# BATT_CONNECTOR.net
KiCad netlist of a schematic drawn in EAGLE
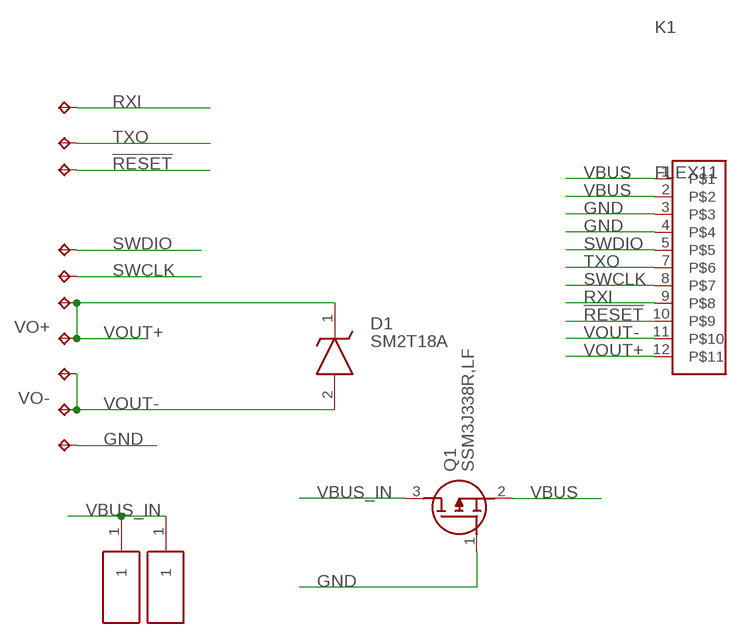
[diagram p0: schematic, sheet 1]

(export (version "E")
  (design (tool "Eeschema 10.0.6"))
  (components
    (comp (ref "!RESET")
      (value "TPB2,54")
      (footprint "eagle-import:B2,54")
      (libsource (lib "eagle-import") (part "TPB2,54"))
    )
    (comp (ref "D1")
      (value "SM2T18A")
      (footprint "eagle-import:SM2T18A")
      (fields (field (name "MOUSER_PART_NUMBER") "511-SM2T18A"))
      (libsource (lib "eagle-import") (part "SM2T18A"))
    )
    (comp (ref "GND")
      (value "TPB2,54")
      (footprint "eagle-import:B2,54")
      (libsource (lib "eagle-import") (part "TPB2,54"))
    )
    (comp (ref "H1")
      (value "S1761-42R")
      (footprint "eagle-import:S176142R")
      (fields (field (name "MOUSER_PART_NUMBER") "855-S1761-42R"))
      (libsource (lib "eagle-import") (part "S1761-42R"))
    )
    (comp (ref "H2")
      (value "S1761-42R")
      (footprint "eagle-import:S176142R")
      (fields (field (name "MOUSER_PART_NUMBER") "855-S1761-42R"))
      (libsource (lib "eagle-import") (part "S1761-42R"))
    )
    (comp (ref "K1")
      (value "FLEX11")
      (footprint "eagle-import:FLEX11")
      (libsource (lib "eagle-import") (part "FLEX11"))
    )
    (comp (ref "Q1")
      (value "SSM3J338R,LF")
      (footprint "eagle-import:SSM3J332RLFT")
      (fields (field (name "MOUSER_PART_NUMBER") "757-SSM3J338RLF"))
      (libsource (lib "eagle-import") (part "SSM3J338R,LF"))
    )
    (comp (ref "RXI")
      (value "TPB2,54")
      (footprint "eagle-import:B2,54")
      (libsource (lib "eagle-import") (part "TPB2,54"))
    )
    (comp (ref "SWCLK")
      (value "TPB2,54")
      (footprint "eagle-import:B2,54")
      (libsource (lib "eagle-import") (part "TPB2,54"))
    )
    (comp (ref "SWDIO")
      (value "TPB2,54")
      (footprint "eagle-import:B2,54")
      (libsource (lib "eagle-import") (part "TPB2,54"))
    )
    (comp (ref "TXO")
      (value "TPB2,54")
      (footprint "eagle-import:B2,54")
      (libsource (lib "eagle-import") (part "TPB2,54"))
    )
    (comp (ref "VO+")
      (value "TPB2,54")
      (footprint "eagle-import:B2,54")
      (libsource (lib "eagle-import") (part "TPB2,54"))
    )
    (comp (ref "VO-")
      (value "TPB2,54")
      (footprint "eagle-import:B2,54")
      (libsource (lib "eagle-import") (part "TPB2,54"))
    )
    (comp (ref "VOUT+1")
      (value "TPB2,54")
      (footprint "eagle-import:B2,54")
      (libsource (lib "eagle-import") (part "TPB2,54"))
    )
    (comp (ref "VOUT-1")
      (value "TPB2,54")
      (footprint "eagle-import:B2,54")
      (libsource (lib "eagle-import") (part "TPB2,54"))
    )
  )
  (nets
    (net (code "1") (name "/GND") (class "Default")
      (node (ref "GND") (pin "TP") (pinfunction "TP_TP") (pintype "input"))
      (node (ref "K1") (pin "3") (pinfunction "P$3_3") (pintype "bidirectional"))
      (node (ref "K1") (pin "4") (pinfunction "P$4_4") (pintype "bidirectional"))
      (node (ref "Q1") (pin "1") (pinfunction "G_1") (pintype "bidirectional"))
    )
    (net (code "2") (name "/RXI") (class "Default")
      (node (ref "K1") (pin "9") (pinfunction "P$8_9") (pintype "bidirectional"))
      (node (ref "RXI") (pin "TP") (pinfunction "TP_TP") (pintype "input"))
    )
    (net (code "3") (name "/SWCLK") (class "Default")
      (node (ref "K1") (pin "8") (pinfunction "P$7_8") (pintype "bidirectional"))
      (node (ref "SWCLK") (pin "TP") (pinfunction "TP_TP") (pintype "input"))
    )
    (net (code "4") (name "/SWDIO") (class "Default")
      (node (ref "K1") (pin "5") (pinfunction "P$5_5") (pintype "bidirectional"))
      (node (ref "SWDIO") (pin "TP") (pinfunction "TP_TP") (pintype "input"))
    )
    (net (code "5") (name "/TXO") (class "Default")
      (node (ref "K1") (pin "7") (pinfunction "P$6_7") (pintype "bidirectional"))
      (node (ref "TXO") (pin "TP") (pinfunction "TP_TP") (pintype "input"))
    )
    (net (code "6") (name "/VBUS") (class "Default")
      (node (ref "K1") (pin "1") (pinfunction "P$1_1") (pintype "bidirectional"))
      (node (ref "K1") (pin "2") (pinfunction "P$2_2") (pintype "bidirectional"))
      (node (ref "Q1") (pin "2") (pinfunction "S_2") (pintype "bidirectional"))
    )
    (net (code "7") (name "/VBUS_IN") (class "Default")
      (node (ref "H1") (pin "1") (pinfunction "1_1") (pintype "bidirectional"))
      (node (ref "H2") (pin "1") (pinfunction "1_1") (pintype "bidirectional"))
      (node (ref "Q1") (pin "3") (pinfunction "D_3") (pintype "bidirectional"))
    )
    (net (code "8") (name "/VOUT+") (class "Default")
      (node (ref "D1") (pin "1") (pinfunction "K_1") (pintype "bidirectional"))
      (node (ref "K1") (pin "12") (pinfunction "P$11_12") (pintype "bidirectional"))
      (node (ref "VO+") (pin "TP") (pinfunction "TP_TP") (pintype "input"))
      (node (ref "VOUT+1") (pin "TP") (pinfunction "TP_TP") (pintype "input"))
    )
    (net (code "9") (name "/VOUT-") (class "Default")
      (node (ref "D1") (pin "2") (pinfunction "A_2") (pintype "bidirectional"))
      (node (ref "K1") (pin "11") (pinfunction "P$10_11") (pintype "bidirectional"))
      (node (ref "VO-") (pin "TP") (pinfunction "TP_TP") (pintype "input"))
      (node (ref "VOUT-1") (pin "TP") (pinfunction "TP_TP") (pintype "input"))
    )
    (net (code "10") (name "/~{RESET}") (class "Default")
      (node (ref "!RESET") (pin "TP") (pinfunction "TP_TP") (pintype "input"))
      (node (ref "K1") (pin "10") (pinfunction "P$9_10") (pintype "bidirectional"))
    )
  )
)
